# 02_som.net
KiCad netlist of a schematic drawn in Altium Designer
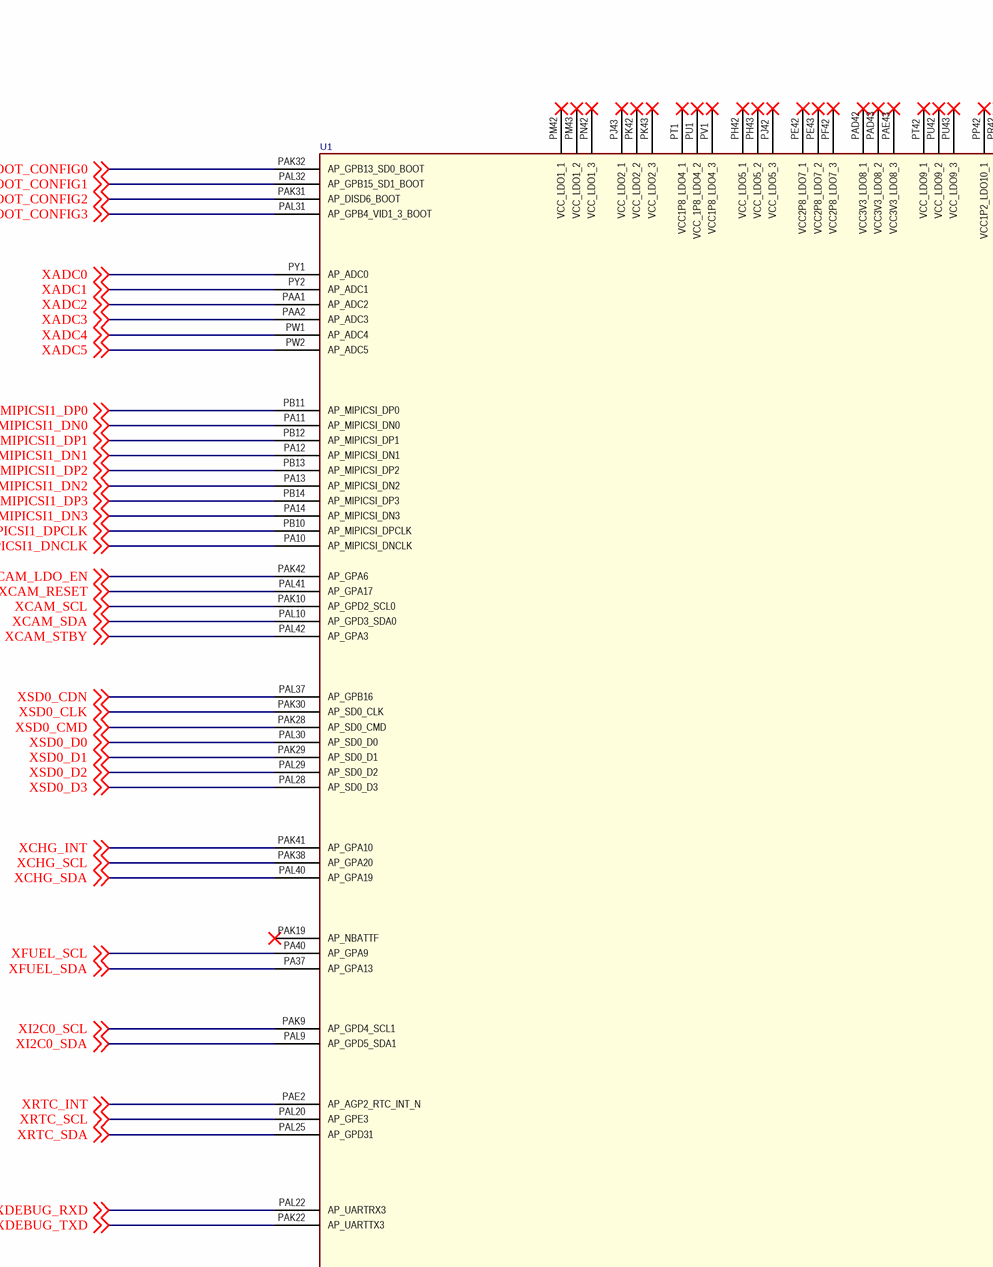
[diagram p0: 02_som.SchDoc, top left]
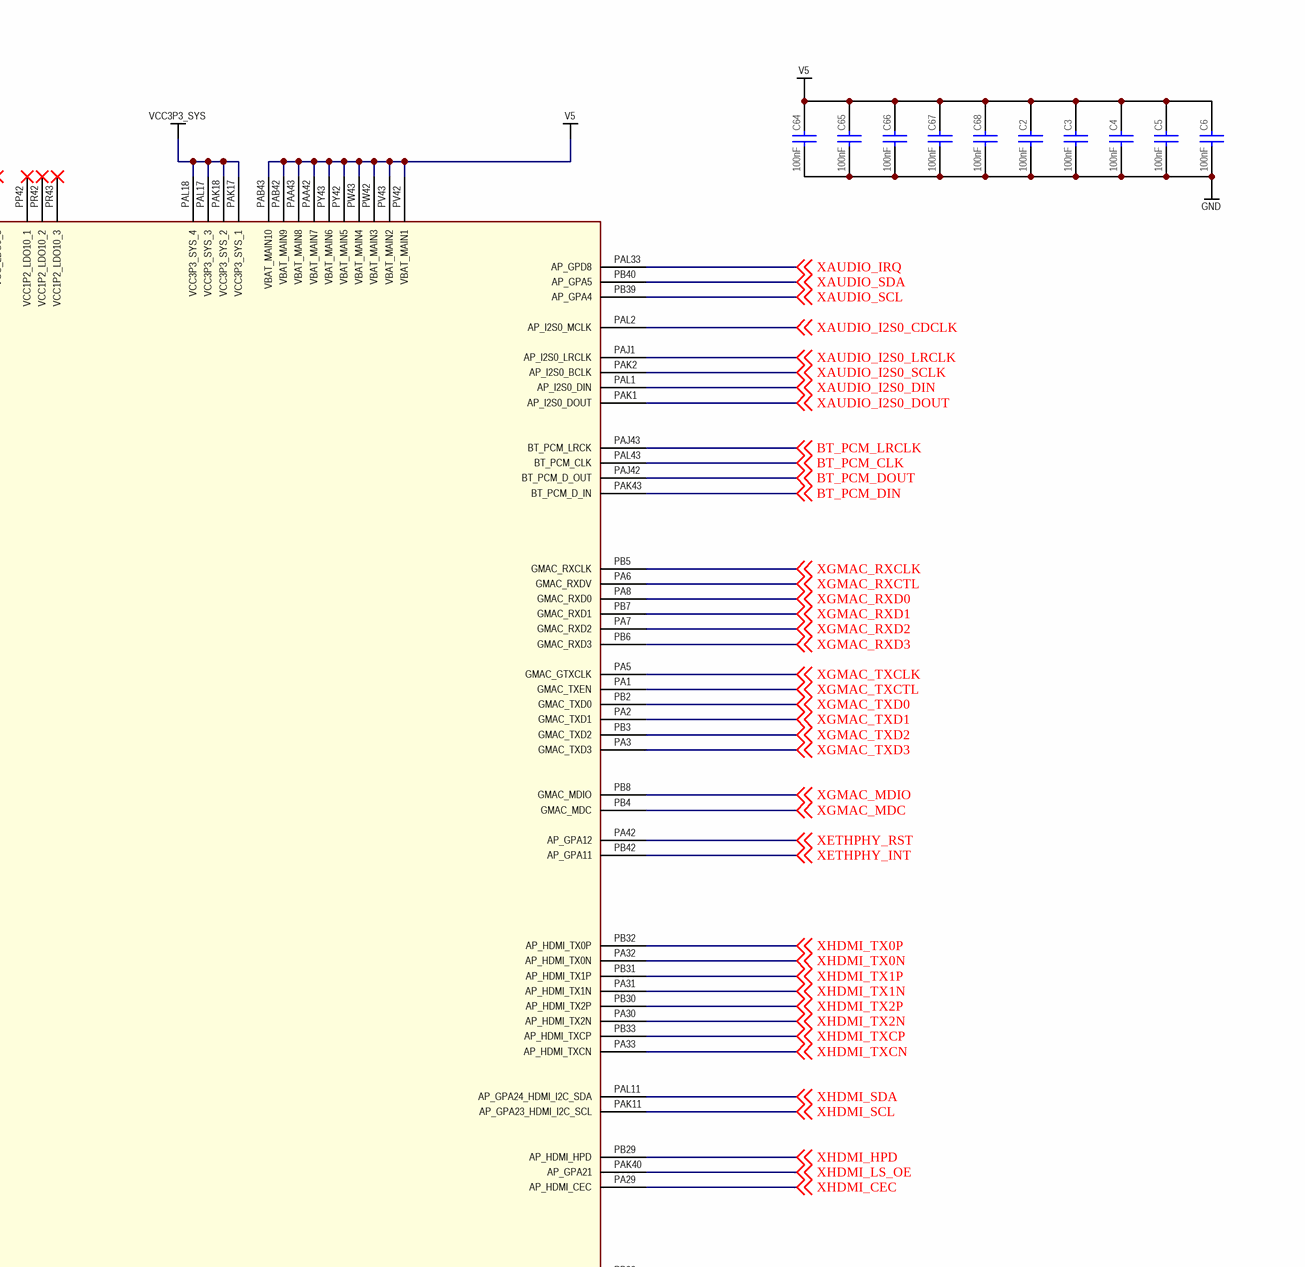
[diagram p1: 02_som.SchDoc, top right]
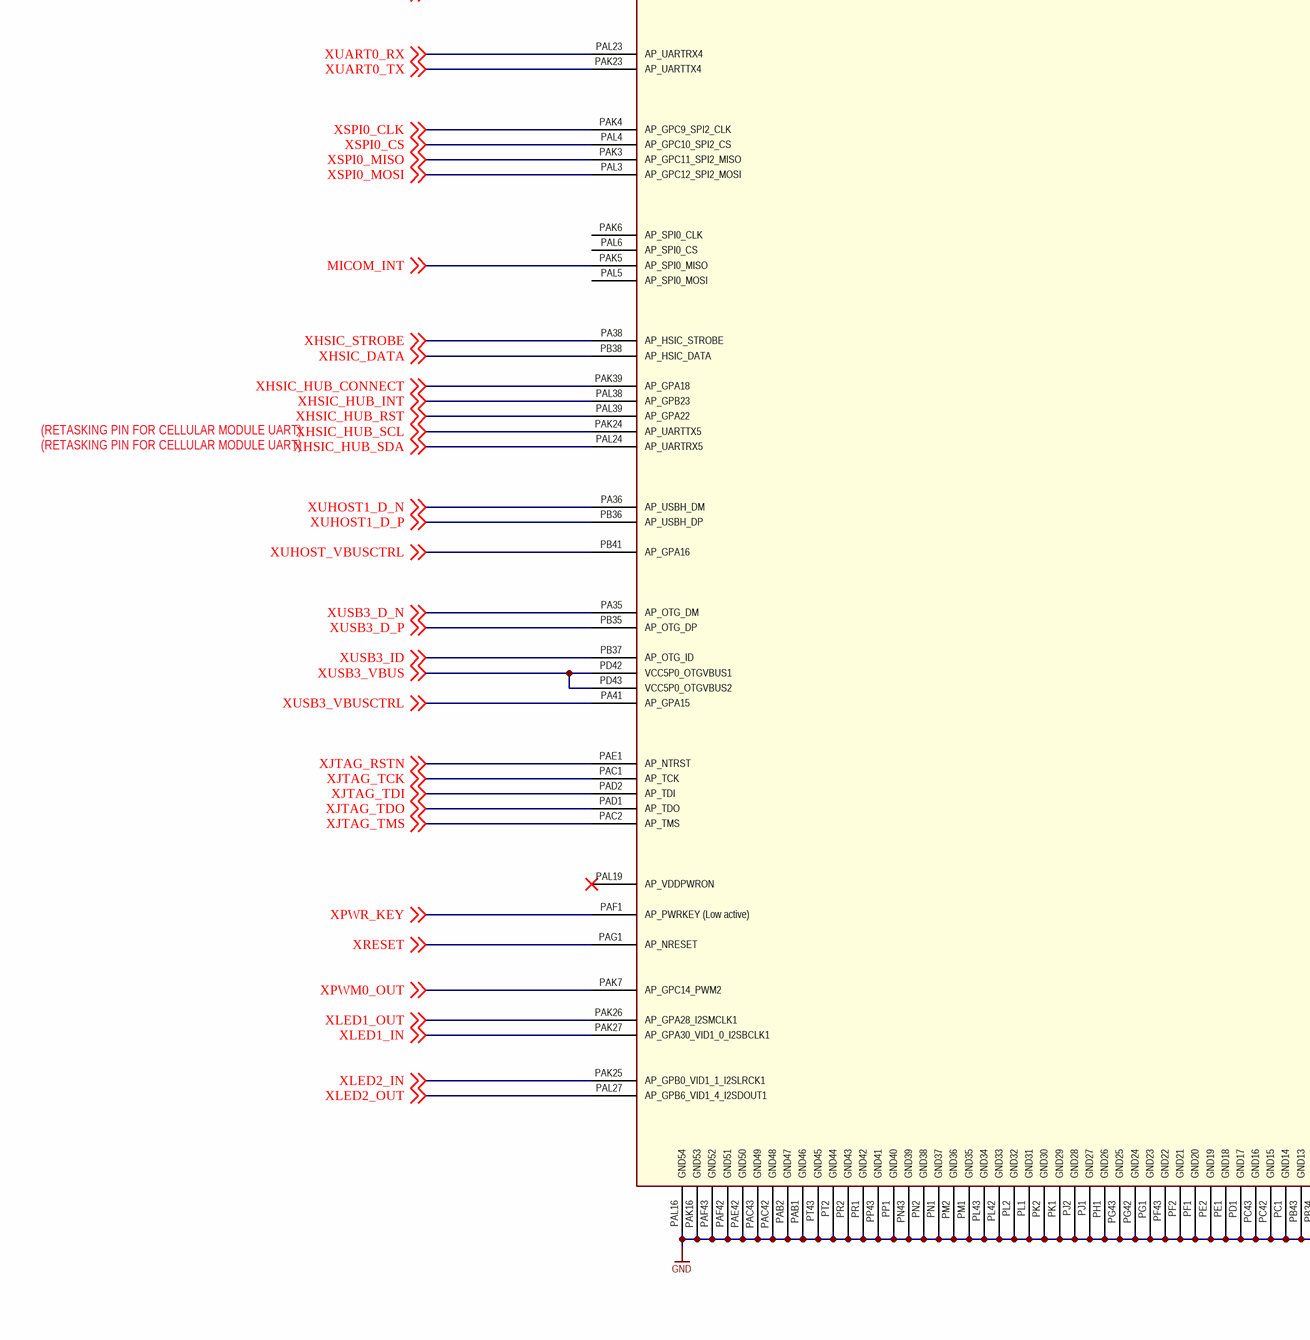
[diagram p2: 02_som.SchDoc, bottom left]
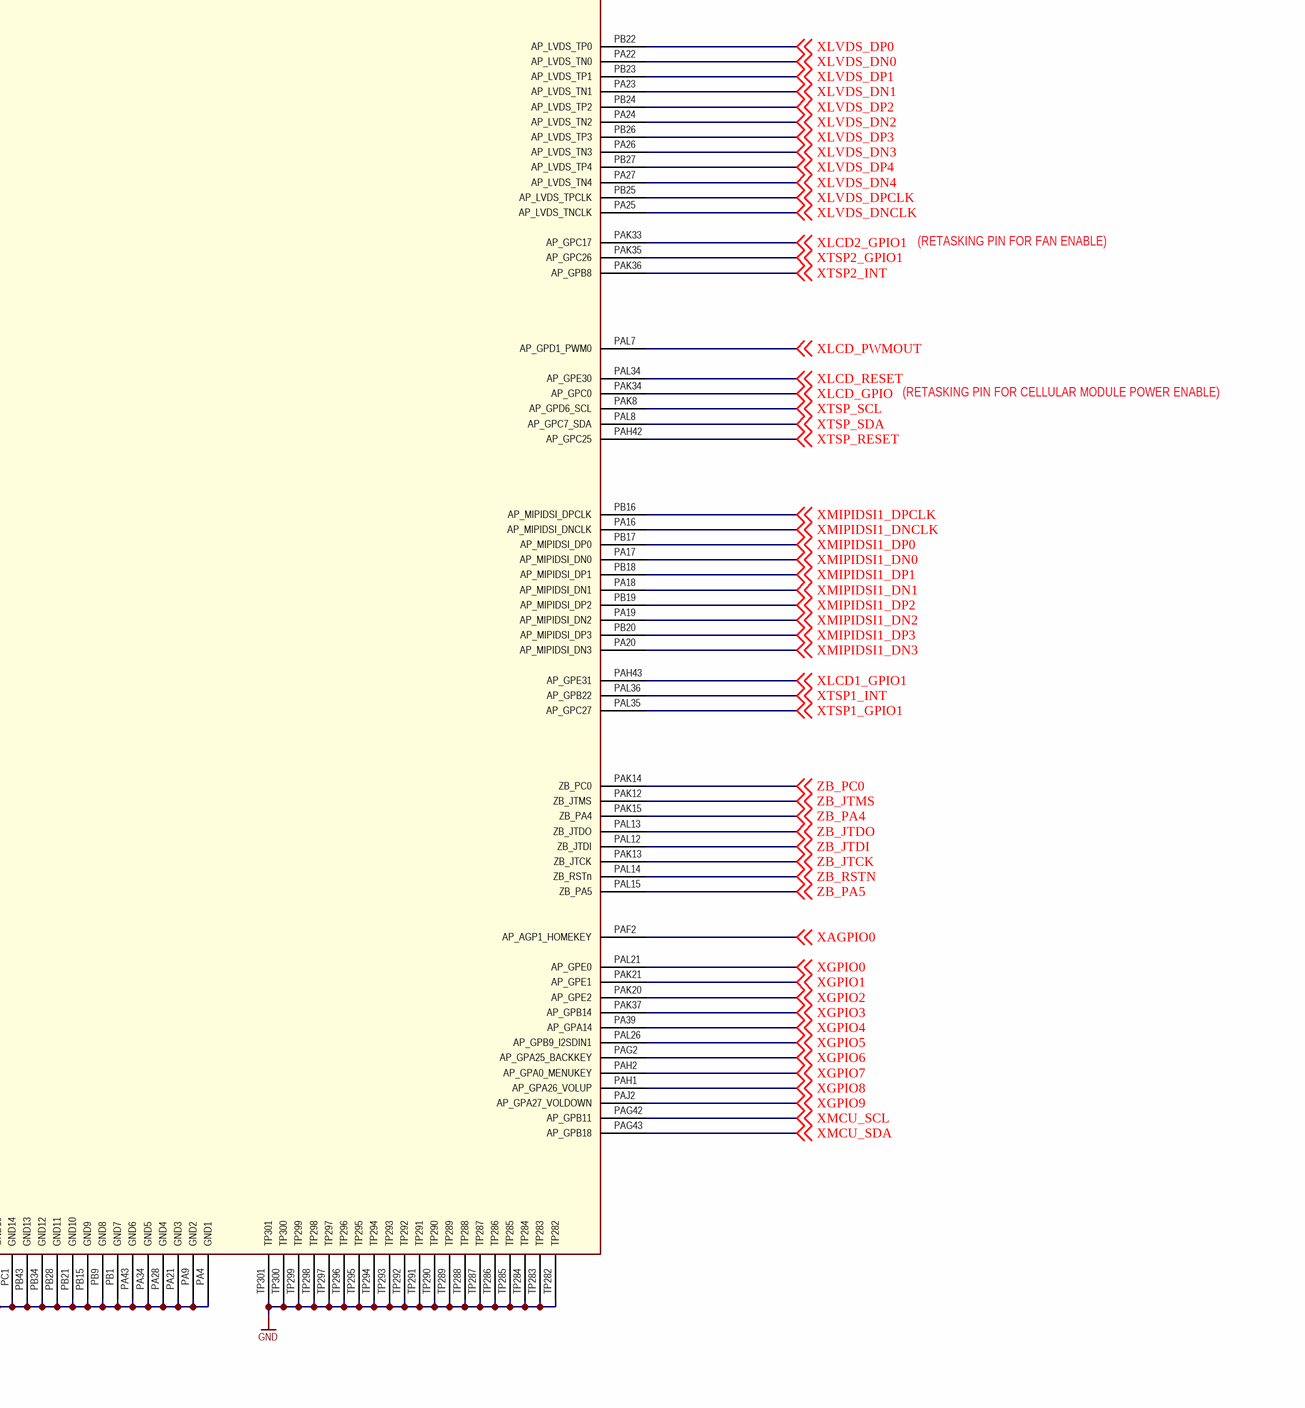
[diagram p3: 02_som.SchDoc, bottom right]

(export (version "E")
  (design (tool "Eeschema 10.0.6"))
  (components
    (comp (ref "C2")
      (value "100nF")
      (footprint "CAPC100X50X55L25N")
      (description "Ceramic Capacitor 100nF ±10% 50V X7R 0402")
      (fields (field (name "MANUFACTURER") "Murata") (field (name "TOLERANCE") "±10%"))
      (libsource (lib "generic") (part "CAP"))
    )
    (comp (ref "C3")
      (value "100nF")
      (footprint "CAPC100X50X55L25N")
      (description "Ceramic Capacitor 100nF ±10% 50V X7R 0402")
      (fields (field (name "MANUFACTURER") "Murata") (field (name "TOLERANCE") "±10%"))
      (libsource (lib "generic") (part "CAP"))
    )
    (comp (ref "C4")
      (value "100nF")
      (footprint "CAPC100X50X55L25N")
      (description "Ceramic Capacitor 100nF ±10% 50V X7R 0402")
      (fields (field (name "MANUFACTURER") "Murata") (field (name "TOLERANCE") "±10%"))
      (libsource (lib "generic") (part "CAP"))
    )
    (comp (ref "C5")
      (value "100nF")
      (footprint "CAPC100X50X55L25N")
      (description "Ceramic Capacitor 100nF ±10% 50V X7R 0402")
      (fields (field (name "MANUFACTURER") "Murata") (field (name "TOLERANCE") "±10%"))
      (libsource (lib "generic") (part "CAP"))
    )
    (comp (ref "C6")
      (value "100nF")
      (footprint "CAPC100X50X55L25N")
      (description "Ceramic Capacitor 100nF ±10% 50V X7R 0402")
      (fields (field (name "MANUFACTURER") "Murata") (field (name "TOLERANCE") "±10%"))
      (libsource (lib "generic") (part "CAP"))
    )
    (comp (ref "C64")
      (value "100nF")
      (footprint "CAPC100X50X55L25N")
      (description "Ceramic Capacitor 100nF ±10% 50V X7R 0402")
      (fields (field (name "MANUFACTURER") "Murata") (field (name "TOLERANCE") "±10%"))
      (libsource (lib "generic") (part "CAP"))
    )
    (comp (ref "C65")
      (value "100nF")
      (footprint "CAPC100X50X55L25N")
      (description "Ceramic Capacitor 100nF ±10% 50V X7R 0402")
      (fields (field (name "MANUFACTURER") "Murata") (field (name "TOLERANCE") "±10%"))
      (libsource (lib "generic") (part "CAP"))
    )
    (comp (ref "C66")
      (value "100nF")
      (footprint "CAPC100X50X55L25N")
      (description "Ceramic Capacitor 100nF ±10% 50V X7R 0402")
      (fields (field (name "MANUFACTURER") "Murata") (field (name "TOLERANCE") "±10%"))
      (libsource (lib "generic") (part "CAP"))
    )
    (comp (ref "C67")
      (value "100nF")
      (footprint "CAPC100X50X55L25N")
      (description "Ceramic Capacitor 100nF ±10% 50V X7R 0402")
      (fields (field (name "MANUFACTURER") "Murata") (field (name "TOLERANCE") "±10%"))
      (libsource (lib "generic") (part "CAP"))
    )
    (comp (ref "C68")
      (value "100nF")
      (footprint "CAPC100X50X55L25N")
      (description "Ceramic Capacitor 100nF ±10% 50V X7R 0402")
      (fields (field (name "MANUFACTURER") "Murata") (field (name "TOLERANCE") "±10%"))
      (libsource (lib "generic") (part "CAP"))
    )
    (comp (ref "U1")
      (value "ARTIK_710_LGA_PAD")
      (footprint "samsung:ARTIK_LGA_PAD_10")
      (description "ARTIK 710 System on Module")
      (fields (field (name "MANUFACTURER") "Samsung"))
      (libsource (lib "*") (part "ARTIK_LGA_PAD_10"))
    )
  )
  (nets
    (net (code "1") (name "BT_PCM_CLK") (class "Default")
      (node (ref "U1") (pin "PAL43") (pinfunction "BT_PCM_CLK_PAL43") (pintype "passive"))
    )
    (net (code "2") (name "BT_PCM_DIN") (class "Default")
      (node (ref "U1") (pin "PAK43") (pinfunction "BT_PCM_D_IN_PAK43") (pintype "passive"))
    )
    (net (code "3") (name "BT_PCM_DOUT") (class "Default")
      (node (ref "U1") (pin "PAJ42") (pinfunction "BT_PCM_D_OUT_PAJ42") (pintype "passive"))
    )
    (net (code "4") (name "BT_PCM_LRCLK") (class "Default")
      (node (ref "U1") (pin "PAJ43") (pinfunction "BT_PCM_LRCK_PAJ43") (pintype "passive"))
    )
    (net (code "5") (name "GND") (class "Default")
      (node (ref "C2") (pin "1") (pinfunction "1_1") (pintype "passive"))
      (node (ref "C3") (pin "1") (pinfunction "1_1") (pintype "passive"))
      (node (ref "C4") (pin "1") (pinfunction "1_1") (pintype "passive"))
      (node (ref "C5") (pin "1") (pinfunction "1_1") (pintype "passive"))
      (node (ref "C6") (pin "1") (pinfunction "1_1") (pintype "passive"))
      (node (ref "C64") (pin "1") (pinfunction "1_1") (pintype "passive"))
      (node (ref "C65") (pin "1") (pinfunction "1_1") (pintype "passive"))
      (node (ref "C66") (pin "1") (pinfunction "1_1") (pintype "passive"))
      (node (ref "C67") (pin "1") (pinfunction "1_1") (pintype "passive"))
      (node (ref "C68") (pin "1") (pinfunction "1_1") (pintype "passive"))
      (node (ref "U1") (pin "PA21") (pinfunction "GND3_PA21") (pintype "passive"))
      (node (ref "U1") (pin "PA28") (pinfunction "GND4_PA28") (pintype "passive"))
      (node (ref "U1") (pin "PA34") (pinfunction "GND5_PA34") (pintype "passive"))
      (node (ref "U1") (pin "PA4") (pinfunction "GND1_PA4") (pintype "passive"))
      (node (ref "U1") (pin "PA43") (pinfunction "GND6_PA43") (pintype "passive"))
      (node (ref "U1") (pin "PA9") (pinfunction "GND2_PA9") (pintype "passive"))
      (node (ref "U1") (pin "PAB1") (pinfunction "GND46_PAB1") (pintype "passive"))
      (node (ref "U1") (pin "PAB2") (pinfunction "GND47_PAB2") (pintype "passive"))
      (node (ref "U1") (pin "PAC42") (pinfunction "GND48_PAC42") (pintype "passive"))
      (node (ref "U1") (pin "PAC43") (pinfunction "GND49_PAC43") (pintype "passive"))
      (node (ref "U1") (pin "PAE42") (pinfunction "GND50_PAE42") (pintype "passive"))
      (node (ref "U1") (pin "PAF42") (pinfunction "GND51_PAF42") (pintype "passive"))
      (node (ref "U1") (pin "PAF43") (pinfunction "GND52_PAF43") (pintype "passive"))
      (node (ref "U1") (pin "PAK16") (pinfunction "GND53_PAK16") (pintype "passive"))
      (node (ref "U1") (pin "PAL16") (pinfunction "GND54_PAL16") (pintype "passive"))
      (node (ref "U1") (pin "PB1") (pinfunction "GND7_PB1") (pintype "passive"))
      (node (ref "U1") (pin "PB15") (pinfunction "GND9_PB15") (pintype "passive"))
      (node (ref "U1") (pin "PB21") (pinfunction "GND10_PB21") (pintype "passive"))
      (node (ref "U1") (pin "PB28") (pinfunction "GND11_PB28") (pintype "passive"))
      (node (ref "U1") (pin "PB34") (pinfunction "GND12_PB34") (pintype "passive"))
      (node (ref "U1") (pin "PB43") (pinfunction "GND13_PB43") (pintype "passive"))
      (node (ref "U1") (pin "PB9") (pinfunction "GND8_PB9") (pintype "passive"))
      (node (ref "U1") (pin "PC1") (pinfunction "GND14_PC1") (pintype "passive"))
      (node (ref "U1") (pin "PC42") (pinfunction "GND15_PC42") (pintype "passive"))
      (node (ref "U1") (pin "PC43") (pinfunction "GND16_PC43") (pintype "passive"))
      (node (ref "U1") (pin "PD1") (pinfunction "GND17_PD1") (pintype "passive"))
      (node (ref "U1") (pin "PE1") (pinfunction "GND18_PE1") (pintype "passive"))
      (node (ref "U1") (pin "PE2") (pinfunction "GND19_PE2") (pintype "passive"))
      (node (ref "U1") (pin "PF1") (pinfunction "GND20_PF1") (pintype "passive"))
      (node (ref "U1") (pin "PF2") (pinfunction "GND21_PF2") (pintype "passive"))
      (node (ref "U1") (pin "PF43") (pinfunction "GND22_PF43") (pintype "passive"))
      (node (ref "U1") (pin "PG1") (pinfunction "GND23_PG1") (pintype "passive"))
      (node (ref "U1") (pin "PG42") (pinfunction "GND24_PG42") (pintype "passive"))
      (node (ref "U1") (pin "PG43") (pinfunction "GND25_PG43") (pintype "passive"))
      (node (ref "U1") (pin "PH1") (pinfunction "GND26_PH1") (pintype "passive"))
      (node (ref "U1") (pin "PJ1") (pinfunction "GND27_PJ1") (pintype "passive"))
      (node (ref "U1") (pin "PJ2") (pinfunction "GND28_PJ2") (pintype "passive"))
      (node (ref "U1") (pin "PK1") (pinfunction "GND29_PK1") (pintype "passive"))
      (node (ref "U1") (pin "PK2") (pinfunction "GND30_PK2") (pintype "passive"))
      (node (ref "U1") (pin "PL1") (pinfunction "GND31_PL1") (pintype "passive"))
      (node (ref "U1") (pin "PL2") (pinfunction "GND32_PL2") (pintype "passive"))
      (node (ref "U1") (pin "PL42") (pinfunction "GND33_PL42") (pintype "passive"))
      (node (ref "U1") (pin "PL43") (pinfunction "GND34_PL43") (pintype "passive"))
      (node (ref "U1") (pin "PM1") (pinfunction "GND35_PM1") (pintype "passive"))
      (node (ref "U1") (pin "PM2") (pinfunction "GND36_PM2") (pintype "passive"))
      (node (ref "U1") (pin "PN1") (pinfunction "GND37_PN1") (pintype "passive"))
      (node (ref "U1") (pin "PN2") (pinfunction "GND38_PN2") (pintype "passive"))
      (node (ref "U1") (pin "PN43") (pinfunction "GND39_PN43") (pintype "passive"))
      (node (ref "U1") (pin "PP1") (pinfunction "GND40_PP1") (pintype "passive"))
      (node (ref "U1") (pin "PP43") (pinfunction "GND41_PP43") (pintype "passive"))
      (node (ref "U1") (pin "PR1") (pinfunction "GND42_PR1") (pintype "passive"))
      (node (ref "U1") (pin "PR2") (pinfunction "GND43_PR2") (pintype "passive"))
      (node (ref "U1") (pin "PT2") (pinfunction "GND44_PT2") (pintype "passive"))
      (node (ref "U1") (pin "PT43") (pinfunction "GND45_PT43") (pintype "passive"))
      (node (ref "U1") (pin "TP282") (pinfunction "TP282_TP282") (pintype "passive"))
      (node (ref "U1") (pin "TP283") (pinfunction "TP283_TP283") (pintype "passive"))
      (node (ref "U1") (pin "TP284") (pinfunction "TP284_TP284") (pintype "passive"))
      (node (ref "U1") (pin "TP285") (pinfunction "TP285_TP285") (pintype "passive"))
      (node (ref "U1") (pin "TP286") (pinfunction "TP286_TP286") (pintype "passive"))
      (node (ref "U1") (pin "TP287") (pinfunction "TP287_TP287") (pintype "passive"))
      (node (ref "U1") (pin "TP288") (pinfunction "TP288_TP288") (pintype "passive"))
      (node (ref "U1") (pin "TP289") (pinfunction "TP289_TP289") (pintype "passive"))
      (node (ref "U1") (pin "TP290") (pinfunction "TP290_TP290") (pintype "passive"))
      (node (ref "U1") (pin "TP291") (pinfunction "TP291_TP291") (pintype "passive"))
      (node (ref "U1") (pin "TP292") (pinfunction "TP292_TP292") (pintype "passive"))
      (node (ref "U1") (pin "TP293") (pinfunction "TP293_TP293") (pintype "passive"))
      (node (ref "U1") (pin "TP294") (pinfunction "TP294_TP294") (pintype "passive"))
      (node (ref "U1") (pin "TP295") (pinfunction "TP295_TP295") (pintype "passive"))
      (node (ref "U1") (pin "TP296") (pinfunction "TP296_TP296") (pintype "passive"))
      (node (ref "U1") (pin "TP297") (pinfunction "TP297_TP297") (pintype "passive"))
      (node (ref "U1") (pin "TP298") (pinfunction "TP298_TP298") (pintype "passive"))
      (node (ref "U1") (pin "TP299") (pinfunction "TP299_TP299") (pintype "passive"))
      (node (ref "U1") (pin "TP300") (pinfunction "TP300_TP300") (pintype "passive"))
      (node (ref "U1") (pin "TP301") (pinfunction "TP301_TP301") (pintype "passive"))
    )
    (net (code "6") (name "MICOM_INT") (class "Default")
      (node (ref "U1") (pin "PAK5") (pinfunction "AP_SPI0_MISO_PAK5") (pintype "passive"))
    )
    (net (code "7") (name "V5") (class "Default")
      (node (ref "C2") (pin "2") (pinfunction "2_2") (pintype "passive"))
      (node (ref "C3") (pin "2") (pinfunction "2_2") (pintype "passive"))
      (node (ref "C4") (pin "2") (pinfunction "2_2") (pintype "passive"))
      (node (ref "C5") (pin "2") (pinfunction "2_2") (pintype "passive"))
      (node (ref "C6") (pin "2") (pinfunction "2_2") (pintype "passive"))
      (node (ref "C64") (pin "2") (pinfunction "2_2") (pintype "passive"))
      (node (ref "C65") (pin "2") (pinfunction "2_2") (pintype "passive"))
      (node (ref "C66") (pin "2") (pinfunction "2_2") (pintype "passive"))
      (node (ref "C67") (pin "2") (pinfunction "2_2") (pintype "passive"))
      (node (ref "C68") (pin "2") (pinfunction "2_2") (pintype "passive"))
      (node (ref "U1") (pin "PAA42") (pinfunction "VBAT_MAIN7_PAA42") (pintype "passive"))
      (node (ref "U1") (pin "PAA43") (pinfunction "VBAT_MAIN8_PAA43") (pintype "passive"))
      (node (ref "U1") (pin "PAB42") (pinfunction "VBAT_MAIN9_PAB42") (pintype "passive"))
      (node (ref "U1") (pin "PAB43") (pinfunction "VBAT_MAIN10_PAB43") (pintype "passive"))
      (node (ref "U1") (pin "PV42") (pinfunction "VBAT_MAIN1_PV42") (pintype "passive"))
      (node (ref "U1") (pin "PV43") (pinfunction "VBAT_MAIN2_PV43") (pintype "passive"))
      (node (ref "U1") (pin "PW42") (pinfunction "VBAT_MAIN3_PW42") (pintype "passive"))
      (node (ref "U1") (pin "PW43") (pinfunction "VBAT_MAIN4_PW43") (pintype "passive"))
      (node (ref "U1") (pin "PY42") (pinfunction "VBAT_MAIN5_PY42") (pintype "passive"))
      (node (ref "U1") (pin "PY43") (pinfunction "VBAT_MAIN6_PY43") (pintype "passive"))
    )
    (net (code "8") (name "VCC3P3_SYS") (class "Default")
      (node (ref "U1") (pin "PAK17") (pinfunction "VCC3P3_SYS_1_PAK17") (pintype "passive"))
      (node (ref "U1") (pin "PAK18") (pinfunction "VCC3P3_SYS_2_PAK18") (pintype "passive"))
      (node (ref "U1") (pin "PAL17") (pinfunction "VCC3P3_SYS_3_PAL17") (pintype "passive"))
      (node (ref "U1") (pin "PAL18") (pinfunction "VCC3P3_SYS_4_PAL18") (pintype "passive"))
    )
    (net (code "9") (name "XADC0") (class "Default")
      (node (ref "U1") (pin "PY1") (pinfunction "AP_ADC0_PY1") (pintype "passive"))
    )
    (net (code "10") (name "XADC1") (class "Default")
      (node (ref "U1") (pin "PY2") (pinfunction "AP_ADC1_PY2") (pintype "passive"))
    )
    (net (code "11") (name "XADC2") (class "Default")
      (node (ref "U1") (pin "PAA1") (pinfunction "AP_ADC2_PAA1") (pintype "passive"))
    )
    (net (code "12") (name "XADC3") (class "Default")
      (node (ref "U1") (pin "PAA2") (pinfunction "AP_ADC3_PAA2") (pintype "passive"))
    )
    (net (code "13") (name "XADC4") (class "Default")
      (node (ref "U1") (pin "PW1") (pinfunction "AP_ADC4_PW1") (pintype "passive"))
    )
    (net (code "14") (name "XADC5") (class "Default")
      (node (ref "U1") (pin "PW2") (pinfunction "AP_ADC5_PW2") (pintype "passive"))
    )
    (net (code "15") (name "XAGPIO0") (class "Default")
      (node (ref "U1") (pin "PAF2") (pinfunction "AP_AGP1_HOMEKEY_PAF2") (pintype "passive"))
    )
    (net (code "16") (name "XAUDIO_I2S0_CDCLK") (class "Default")
      (node (ref "U1") (pin "PAL2") (pinfunction "AP_I2S0_MCLK_PAL2") (pintype "passive"))
    )
    (net (code "17") (name "XAUDIO_I2S0_DIN") (class "Default")
      (node (ref "U1") (pin "PAL1") (pinfunction "AP_I2S0_DIN_PAL1") (pintype "passive"))
    )
    (net (code "18") (name "XAUDIO_I2S0_DOUT") (class "Default")
      (node (ref "U1") (pin "PAK1") (pinfunction "AP_I2S0_DOUT_PAK1") (pintype "passive"))
    )
    (net (code "19") (name "XAUDIO_I2S0_LRCLK") (class "Default")
      (node (ref "U1") (pin "PAJ1") (pinfunction "AP_I2S0_LRCLK_PAJ1") (pintype "passive"))
    )
    (net (code "20") (name "XAUDIO_I2S0_SCLK") (class "Default")
      (node (ref "U1") (pin "PAK2") (pinfunction "AP_I2S0_BCLK_PAK2") (pintype "passive"))
    )
    (net (code "21") (name "XAUDIO_IRQ") (class "Default")
      (node (ref "U1") (pin "PAL33") (pinfunction "AP_GPD8_PAL33") (pintype "passive"))
    )
    (net (code "22") (name "XAUDIO_SCL") (class "Default")
      (node (ref "U1") (pin "PB39") (pinfunction "AP_GPA4_PB39") (pintype "passive"))
    )
    (net (code "23") (name "XAUDIO_SDA") (class "Default")
      (node (ref "U1") (pin "PB40") (pinfunction "AP_GPA5_PB40") (pintype "passive"))
    )
    (net (code "24") (name "XBOOT_CONFIG0") (class "Default")
      (node (ref "U1") (pin "PAK32") (pinfunction "AP_GPB13_SD0_BOOT_PAK32") (pintype "passive"))
    )
    (net (code "25") (name "XBOOT_CONFIG1") (class "Default")
      (node (ref "U1") (pin "PAL32") (pinfunction "AP_GPB15_SD1_BOOT_PAL32") (pintype "passive"))
    )
    (net (code "26") (name "XBOOT_CONFIG2") (class "Default")
      (node (ref "U1") (pin "PAK31") (pinfunction "AP_DISD6_BOOT_PAK31") (pintype "passive"))
    )
    (net (code "27") (name "XBOOT_CONFIG3") (class "Default")
      (node (ref "U1") (pin "PAL31") (pinfunction "AP_GPB4_VID1_3_BOOT_PAL31") (pintype "passive"))
    )
    (net (code "28") (name "XCAM_LDO_EN") (class "Default")
      (node (ref "U1") (pin "PAK42") (pinfunction "AP_GPA6_PAK42") (pintype "passive"))
    )
    (net (code "29") (name "XCAM_RESET") (class "Default")
      (node (ref "U1") (pin "PAL41") (pinfunction "AP_GPA17_PAL41") (pintype "passive"))
    )
    (net (code "30") (name "XCAM_SCL") (class "Default")
      (node (ref "U1") (pin "PAK10") (pinfunction "AP_GPD2_SCL0_PAK10") (pintype "passive"))
    )
    (net (code "31") (name "XCAM_SDA") (class "Default")
      (node (ref "U1") (pin "PAL10") (pinfunction "AP_GPD3_SDA0_PAL10") (pintype "passive"))
    )
    (net (code "32") (name "XCAM_STBY") (class "Default")
      (node (ref "U1") (pin "PAL42") (pinfunction "AP_GPA3_PAL42") (pintype "passive"))
    )
    (net (code "33") (name "XCHG_INT") (class "Default")
      (node (ref "U1") (pin "PAK41") (pinfunction "AP_GPA10_PAK41") (pintype "passive"))
    )
    (net (code "34") (name "XCHG_SCL") (class "Default")
      (node (ref "U1") (pin "PAK38") (pinfunction "AP_GPA20_PAK38") (pintype "passive"))
    )
    (net (code "35") (name "XCHG_SDA") (class "Default")
      (node (ref "U1") (pin "PAL40") (pinfunction "AP_GPA19_PAL40") (pintype "passive"))
    )
    (net (code "36") (name "XDEBUG_RXD") (class "Default")
      (node (ref "U1") (pin "PAL22") (pinfunction "AP_UARTRX3_PAL22") (pintype "passive"))
    )
    (net (code "37") (name "XDEBUG_TXD") (class "Default")
      (node (ref "U1") (pin "PAK22") (pinfunction "AP_UARTTX3_PAK22") (pintype "passive"))
    )
    (net (code "38") (name "XETHPHY_INT") (class "Default")
      (node (ref "U1") (pin "PB42") (pinfunction "AP_GPA11_PB42") (pintype "passive"))
    )
    (net (code "39") (name "XETHPHY_RST") (class "Default")
      (node (ref "U1") (pin "PA42") (pinfunction "AP_GPA12_PA42") (pintype "passive"))
    )
    (net (code "40") (name "XFUEL_SCL") (class "Default")
      (node (ref "U1") (pin "PA40") (pinfunction "AP_GPA9_PA40") (pintype "passive"))
    )
    (net (code "41") (name "XFUEL_SDA") (class "Default")
      (node (ref "U1") (pin "PA37") (pinfunction "AP_GPA13_PA37") (pintype "passive"))
    )
    (net (code "42") (name "XGMAC_MDC") (class "Default")
      (node (ref "U1") (pin "PB4") (pinfunction "GMAC_MDC_PB4") (pintype "passive"))
    )
    (net (code "43") (name "XGMAC_MDIO") (class "Default")
      (node (ref "U1") (pin "PB8") (pinfunction "GMAC_MDIO_PB8") (pintype "passive"))
    )
    (net (code "44") (name "XGMAC_RXCLK") (class "Default")
      (node (ref "U1") (pin "PB5") (pinfunction "GMAC_RXCLK_PB5") (pintype "passive"))
    )
    (net (code "45") (name "XGMAC_RXCTL") (class "Default")
      (node (ref "U1") (pin "PA6") (pinfunction "GMAC_RXDV_PA6") (pintype "passive"))
    )
    (net (code "46") (name "XGMAC_RXD0") (class "Default")
      (node (ref "U1") (pin "PA8") (pinfunction "GMAC_RXD0_PA8") (pintype "passive"))
    )
    (net (code "47") (name "XGMAC_RXD1") (class "Default")
      (node (ref "U1") (pin "PB7") (pinfunction "GMAC_RXD1_PB7") (pintype "passive"))
    )
    (net (code "48") (name "XGMAC_RXD2") (class "Default")
      (node (ref "U1") (pin "PA7") (pinfunction "GMAC_RXD2_PA7") (pintype "passive"))
    )
    (net (code "49") (name "XGMAC_RXD3") (class "Default")
      (node (ref "U1") (pin "PB6") (pinfunction "GMAC_RXD3_PB6") (pintype "passive"))
    )
    (net (code "50") (name "XGMAC_TXCLK") (class "Default")
      (node (ref "U1") (pin "PA5") (pinfunction "GMAC_GTXCLK_PA5") (pintype "passive"))
    )
    (net (code "51") (name "XGMAC_TXCTL") (class "Default")
      (node (ref "U1") (pin "PA1") (pinfunction "GMAC_TXEN_PA1") (pintype "passive"))
    )
    (net (code "52") (name "XGMAC_TXD0") (class "Default")
      (node (ref "U1") (pin "PB2") (pinfunction "GMAC_TXD0_PB2") (pintype "passive"))
    )
    (net (code "53") (name "XGMAC_TXD1") (class "Default")
      (node (ref "U1") (pin "PA2") (pinfunction "GMAC_TXD1_PA2") (pintype "passive"))
    )
    (net (code "54") (name "XGMAC_TXD2") (class "Default")
      (node (ref "U1") (pin "PB3") (pinfunction "GMAC_TXD2_PB3") (pintype "passive"))
    )
    (net (code "55") (name "XGMAC_TXD3") (class "Default")
      (node (ref "U1") (pin "PA3") (pinfunction "GMAC_TXD3_PA3") (pintype "passive"))
    )
    (net (code "56") (name "XGPIO0") (class "Default")
      (node (ref "U1") (pin "PAL21") (pinfunction "AP_GPE0_PAL21") (pintype "passive"))
    )
    (net (code "57") (name "XGPIO1") (class "Default")
      (node (ref "U1") (pin "PAK21") (pinfunction "AP_GPE1_PAK21") (pintype "passive"))
    )
    (net (code "58") (name "XGPIO2") (class "Default")
      (node (ref "U1") (pin "PAK20") (pinfunction "AP_GPE2_PAK20") (pintype "passive"))
    )
    (net (code "59") (name "XGPIO3") (class "Default")
      (node (ref "U1") (pin "PAK37") (pinfunction "AP_GPB14_PAK37") (pintype "passive"))
    )
    (net (code "60") (name "XGPIO4") (class "Default")
      (node (ref "U1") (pin "PA39") (pinfunction "AP_GPA14_PA39") (pintype "passive"))
    )
    (net (code "61") (name "XGPIO5") (class "Default")
      (node (ref "U1") (pin "PAL26") (pinfunction "AP_GPB9_I2SDIN1_PAL26") (pintype "passive"))
    )
    (net (code "62") (name "XGPIO6") (class "Default")
      (node (ref "U1") (pin "PAG2") (pinfunction "AP_GPA25_BACKKEY_PAG2") (pintype "passive"))
    )
    (net (code "63") (name "XGPIO7") (class "Default")
      (node (ref "U1") (pin "PAH2") (pinfunction "AP_GPA0_MENUKEY_PAH2") (pintype "passive"))
    )
    (net (code "64") (name "XGPIO8") (class "Default")
      (node (ref "U1") (pin "PAH1") (pinfunction "AP_GPA26_VOLUP_PAH1") (pintype "passive"))
    )
    (net (code "65") (name "XGPIO9") (class "Default")
      (node (ref "U1") (pin "PAJ2") (pinfunction "AP_GPA27_VOLDOWN_PAJ2") (pintype "passive"))
    )
    (net (code "66") (name "XHDMI_CEC") (class "Default")
      (node (ref "U1") (pin "PA29") (pinfunction "AP_HDMI_CEC_PA29") (pintype "passive"))
    )
    (net (code "67") (name "XHDMI_HPD") (class "Default")
      (node (ref "U1") (pin "PB29") (pinfunction "AP_HDMI_HPD_PB29") (pintype "passive"))
    )
    (net (code "68") (name "XHDMI_LS_OE") (class "Default")
      (node (ref "U1") (pin "PAK40") (pinfunction "AP_GPA21_PAK40") (pintype "passive"))
    )
    (net (code "69") (name "XHDMI_SCL") (class "Default")
      (node (ref "U1") (pin "PAK11") (pinfunction "AP_GPA23_HDMI_I2C_SCL_PAK11") (pintype "passive"))
    )
    (net (code "70") (name "XHDMI_SDA") (class "Default")
      (node (ref "U1") (pin "PAL11") (pinfunction "AP_GPA24_HDMI_I2C_SDA_PAL11") (pintype "passive"))
    )
    (net (code "71") (name "XHDMI_TX0N") (class "Default")
      (node (ref "U1") (pin "PA32") (pinfunction "AP_HDMI_TX0N_PA32") (pintype "passive"))
    )
    (net (code "72") (name "XHDMI_TX0P") (class "Default")
      (node (ref "U1") (pin "PB32") (pinfunction "AP_HDMI_TX0P_PB32") (pintype "passive"))
    )
    (net (code "73") (name "XHDMI_TX1N") (class "Default")
      (node (ref "U1") (pin "PA31") (pinfunction "AP_HDMI_TX1N_PA31") (pintype "passive"))
    )
    (net (code "74") (name "XHDMI_TX1P") (class "Default")
      (node (ref "U1") (pin "PB31") (pinfunction "AP_HDMI_TX1P_PB31") (pintype "passive"))
    )
    (net (code "75") (name "XHDMI_TX2N") (class "Default")
      (node (ref "U1") (pin "PA30") (pinfunction "AP_HDMI_TX2N_PA30") (pintype "passive"))
    )
    (net (code "76") (name "XHDMI_TX2P") (class "Default")
      (node (ref "U1") (pin "PB30") (pinfunction "AP_HDMI_TX2P_PB30") (pintype "passive"))
    )
    (net (code "77") (name "XHDMI_TXCN") (class "Default")
      (node (ref "U1") (pin "PA33") (pinfunction "AP_HDMI_TXCN_PA33") (pintype "passive"))
    )
    (net (code "78") (name "XHDMI_TXCP") (class "Default")
      (node (ref "U1") (pin "PB33") (pinfunction "AP_HDMI_TXCP_PB33") (pintype "passive"))
    )
    (net (code "79") (name "XHSIC_DATA") (class "Default")
      (node (ref "U1") (pin "PB38") (pinfunction "AP_HSIC_DATA_PB38") (pintype "passive"))
    )
    (net (code "80") (name "XHSIC_HUB_CONNECT") (class "Default")
      (node (ref "U1") (pin "PAK39") (pinfunction "AP_GPA18_PAK39") (pintype "passive"))
    )
    (net (code "81") (name "XHSIC_HUB_INT") (class "Default")
      (node (ref "U1") (pin "PAL38") (pinfunction "AP_GPB23_PAL38") (pintype "passive"))
    )
    (net (code "82") (name "XHSIC_HUB_RST") (class "Default")
      (node (ref "U1") (pin "PAL39") (pinfunction "AP_GPA22_PAL39") (pintype "passive"))
    )
    (net (code "83") (name "XHSIC_HUB_SCL") (class "Default")
      (node (ref "U1") (pin "PAK24") (pinfunction "AP_UARTTX5_PAK24") (pintype "passive"))
    )
    (net (code "84") (name "XHSIC_HUB_SDA") (class "Default")
      (node (ref "U1") (pin "PAL24") (pinfunction "AP_UARTRX5_PAL24") (pintype "passive"))
    )
    (net (code "85") (name "XHSIC_STROBE") (class "Default")
      (node (ref "U1") (pin "PA38") (pinfunction "AP_HSIC_STROBE_PA38") (pintype "passive"))
    )
    (net (code "86") (name "XI2C0_SCL") (class "Default")
      (node (ref "U1") (pin "PAK9") (pinfunction "AP_GPD4_SCL1_PAK9") (pintype "passive"))
    )
    (net (code "87") (name "XI2C0_SDA") (class "Default")
      (node (ref "U1") (pin "PAL9") (pinfunction "AP_GPD5_SDA1_PAL9") (pintype "passive"))
    )
    (net (code "88") (name "XJTAG_RSTN") (class "Default")
      (node (ref "U1") (pin "PAE1") (pinfunction "AP_NTRST_PAE1") (pintype "passive"))
    )
    (net (code "89") (name "XJTAG_TCK") (class "Default")
      (node (ref "U1") (pin "PAC1") (pinfunction "AP_TCK_PAC1") (pintype "passive"))
    )
    (net (code "90") (name "XJTAG_TDI") (class "Default")
      (node (ref "U1") (pin "PAD2") (pinfunction "AP_TDI_PAD2") (pintype "passive"))
    )
    (net (code "91") (name "XJTAG_TDO") (class "Default")
      (node (ref "U1") (pin "PAD1") (pinfunction "AP_TDO_PAD1") (pintype "passive"))
    )
    (net (code "92") (name "XJTAG_TMS") (class "Default")
      (node (ref "U1") (pin "PAC2") (pinfunction "AP_TMS_PAC2") (pintype "passive"))
    )
    (net (code "93") (name "XLCD1_GPIO1") (class "Default")
      (node (ref "U1") (pin "PAH43") (pinfunction "AP_GPE31_PAH43") (pintype "passive"))
    )
    (net (code "94") (name "XLCD2_GPIO1") (class "Default")
      (node (ref "U1") (pin "PAK33") (pinfunction "AP_GPC17_PAK33") (pintype "passive"))
    )
    (net (code "95") (name "XLCD_GPIO") (class "Default")
      (node (ref "U1") (pin "PAK34") (pinfunction "AP_GPC0_PAK34") (pintype "passive"))
    )
    (net (code "96") (name "XLCD_PWMOUT") (class "Default")
      (node (ref "U1") (pin "PAL7") (pinfunction "AP_GPD1_PWM0_PAL7") (pintype "passive"))
    )
    (net (code "97") (name "XLCD_RESET") (class "Default")
      (node (ref "U1") (pin "PAL34") (pinfunction "AP_GPE30_PAL34") (pintype "passive"))
    )
    (net (code "98") (name "XLED1_IN") (class "Default")
      (node (ref "U1") (pin "PAK27") (pinfunction "AP_GPA30_VID1_0_I2SBCLK1_PAK27") (pintype "passive"))
    )
    (net (code "99") (name "XLED1_OUT") (class "Default")
      (node (ref "U1") (pin "PAK26") (pinfunction "AP_GPA28_I2SMCLK1_PAK26") (pintype "passive"))
    )
    (net (code "100") (name "XLED2_IN") (class "Default")
      (node (ref "U1") (pin "PAK25") (pinfunction "AP_GPB0_VID1_1_I2SLRCK1_PAK25") (pintype "passive"))
    )
    (net (code "101") (name "XLED2_OUT") (class "Default")
      (node (ref "U1") (pin "PAL27") (pinfunction "AP_GPB6_VID1_4_I2SDOUT1_PAL27") (pintype "passive"))
    )
    (net (code "102") (name "XLVDS_DN0") (class "Default")
      (node (ref "U1") (pin "PA22") (pinfunction "AP_LVDS_TN0_PA22") (pintype "passive"))
    )
    (net (code "103") (name "XLVDS_DN1") (class "Default")
      (node (ref "U1") (pin "PA23") (pinfunction "AP_LVDS_TN1_PA23") (pintype "passive"))
    )
    (net (code "104") (name "XLVDS_DN2") (class "Default")
      (node (ref "U1") (pin "PA24") (pinfunction "AP_LVDS_TN2_PA24") (pintype "passive"))
    )
    (net (code "105") (name "XLVDS_DN3") (class "Default")
      (node (ref "U1") (pin "PA26") (pinfunction "AP_LVDS_TN3_PA26") (pintype "passive"))
    )
    (net (code "106") (name "XLVDS_DN4") (class "Default")
      (node (ref "U1") (pin "PA27") (pinfunction "AP_LVDS_TN4_PA27") (pintype "passive"))
    )
    (net (code "107") (name "XLVDS_DNCLK") (class "Default")
      (node (ref "U1") (pin "PA25") (pinfunction "AP_LVDS_TNCLK_PA25") (pintype "passive"))
    )
    (net (code "108") (name "XLVDS_DP0") (class "Default")
      (node (ref "U1") (pin "PB22") (pinfunction "AP_LVDS_TP0_PB22") (pintype "passive"))
    )
    (net (code "109") (name "XLVDS_DP1") (class "Default")
      (node (ref "U1") (pin "PB23") (pinfunction "AP_LVDS_TP1_PB23") (pintype "passive"))
    )
    (net (code "110") (name "XLVDS_DP2") (class "Default")
      (node (ref "U1") (pin "PB24") (pinfunction "AP_LVDS_TP2_PB24") (pintype "passive"))
    )
    (net (code "111") (name "XLVDS_DP3") (class "Default")
      (node (ref "U1") (pin "PB26") (pinfunction "AP_LVDS_TP3_PB26") (pintype "passive"))
    )
    (net (code "112") (name "XLVDS_DP4") (class "Default")
      (node (ref "U1") (pin "PB27") (pinfunction "AP_LVDS_TP4_PB27") (pintype "passive"))
    )
    (net (code "113") (name "XLVDS_DPCLK") (class "Default")
      (node (ref "U1") (pin "PB25") (pinfunction "AP_LVDS_TPCLK_PB25") (pintype "passive"))
    )
    (net (code "114") (name "XMCU_SCL") (class "Default")
      (node (ref "U1") (pin "PAG42") (pinfunction "AP_GPB11_PAG42") (pintype "passive"))
    )
    (net (code "115") (name "XMCU_SDA") (class "Default")
      (node (ref "U1") (pin "PAG43") (pinfunction "AP_GPB18_PAG43") (pintype "passive"))
    )
    (net (code "116") (name "XMIPICSI1_DN0") (class "Default")
      (node (ref "U1") (pin "PA11") (pinfunction "AP_MIPICSI_DN0_PA11") (pintype "passive"))
    )
    (net (code "117") (name "XMIPICSI1_DN1") (class "Default")
      (node (ref "U1") (pin "PA12") (pinfunction "AP_MIPICSI_DN1_PA12") (pintype "passive"))
    )
    (net (code "118") (name "XMIPICSI1_DN2") (class "Default")
      (node (ref "U1") (pin "PA13") (pinfunction "AP_MIPICSI_DN2_PA13") (pintype "passive"))
    )
    (net (code "119") (name "XMIPICSI1_DN3") (class "Default")
      (node (ref "U1") (pin "PA14") (pinfunction "AP_MIPICSI_DN3_PA14") (pintype "passive"))
    )
    (net (code "120") (name "XMIPICSI1_DNCLK") (class "Default")
      (node (ref "U1") (pin "PA10") (pinfunction "AP_MIPICSI_DNCLK_PA10") (pintype "passive"))
    )
    (net (code "121") (name "XMIPICSI1_DP0") (class "Default")
      (node (ref "U1") (pin "PB11") (pinfunction "AP_MIPICSI_DP0_PB11") (pintype "passive"))
    )
    (net (code "122") (name "XMIPICSI1_DP1") (class "Default")
      (node (ref "U1") (pin "PB12") (pinfunction "AP_MIPICSI_DP1_PB12") (pintype "passive"))
    )
    (net (code "123") (name "XMIPICSI1_DP2") (class "Default")
      (node (ref "U1") (pin "PB13") (pinfunction "AP_MIPICSI_DP2_PB13") (pintype "passive"))
    )
    (net (code "124") (name "XMIPICSI1_DP3") (class "Default")
      (node (ref "U1") (pin "PB14") (pinfunction "AP_MIPICSI_DP3_PB14") (pintype "passive"))
    )
    (net (code "125") (name "XMIPICSI1_DPCLK") (class "Default")
      (node (ref "U1") (pin "PB10") (pinfunction "AP_MIPICSI_DPCLK_PB10") (pintype "passive"))
    )
    (net (code "126") (name "XMIPIDSI1_DN0") (class "Default")
      (node (ref "U1") (pin "PA17") (pinfunction "AP_MIPIDSI_DN0_PA17") (pintype "passive"))
    )
    (net (code "127") (name "XMIPIDSI1_DN1") (class "Default")
      (node (ref "U1") (pin "PA18") (pinfunction "AP_MIPIDSI_DN1_PA18") (pintype "passive"))
    )
    (net (code "128") (name "XMIPIDSI1_DN2") (class "Default")
      (node (ref "U1") (pin "PA19") (pinfunction "AP_MIPIDSI_DN2_PA19") (pintype "passive"))
    )
    (net (code "129") (name "XMIPIDSI1_DN3") (class "Default")
      (node (ref "U1") (pin "PA20") (pinfunction "AP_MIPIDSI_DN3_PA20") (pintype "passive"))
    )
    (net (code "130") (name "XMIPIDSI1_DNCLK") (class "Default")
      (node (ref "U1") (pin "PA16") (pinfunction "AP_MIPIDSI_DNCLK_PA16") (pintype "passive"))
    )
    (net (code "131") (name "XMIPIDSI1_DP0") (class "Default")
      (node (ref "U1") (pin "PB17") (pinfunction "AP_MIPIDSI_DP0_PB17") (pintype "passive"))
    )
    (net (code "132") (name "XMIPIDSI1_DP1") (class "Default")
      (node (ref "U1") (pin "PB18") (pinfunction "AP_MIPIDSI_DP1_PB18") (pintype "passive"))
    )
    (net (code "133") (name "XMIPIDSI1_DP2") (class "Default")
      (node (ref "U1") (pin "PB19") (pinfunction "AP_MIPIDSI_DP2_PB19") (pintype "passive"))
    )
    (net (code "134") (name "XMIPIDSI1_DP3") (class "Default")
      (node (ref "U1") (pin "PB20") (pinfunction "AP_MIPIDSI_DP3_PB20") (pintype "passive"))
    )
    (net (code "135") (name "XMIPIDSI1_DPCLK") (class "Default")
      (node (ref "U1") (pin "PB16") (pinfunction "AP_MIPIDSI_DPCLK_PB16") (pintype "passive"))
    )
    (net (code "136") (name "XPWM0_OUT") (class "Default")
      (node (ref "U1") (pin "PAK7") (pinfunction "AP_GPC14_PWM2_PAK7") (pintype "passive"))
    )
    (net (code "137") (name "XPWR_KEY") (class "Default")
      (node (ref "U1") (pin "PAF1") (pinfunction "AP_PWRKEY_(Low_active)_PAF1") (pintype "passive"))
    )
    (net (code "138") (name "XRESET") (class "Default")
      (node (ref "U1") (pin "PAG1") (pinfunction "AP_NRESET_PAG1") (pintype "passive"))
    )
    (net (code "139") (name "XRTC_INT") (class "Default")
      (node (ref "U1") (pin "PAE2") (pinfunction "AP_AGP2_RTC_INT_N_PAE2") (pintype "passive"))
    )
    (net (code "140") (name "XRTC_SCL") (class "Default")
      (node (ref "U1") (pin "PAL20") (pinfunction "AP_GPE3_PAL20") (pintype "passive"))
    )
    (net (code "141") (name "XRTC_SDA") (class "Default")
      (node (ref "U1") (pin "PAL25") (pinfunction "AP_GPD31_PAL25") (pintype "passive"))
    )
    (net (code "142") (name "XSD0_CDN") (class "Default")
      (node (ref "U1") (pin "PAL37") (pinfunction "AP_GPB16_PAL37") (pintype "passive"))
    )
    (net (code "143") (name "XSD0_CLK") (class "Default")
      (node (ref "U1") (pin "PAK30") (pinfunction "AP_SD0_CLK_PAK30") (pintype "passive"))
    )
    (net (code "144") (name "XSD0_CMD") (class "Default")
      (node (ref "U1") (pin "PAK28") (pinfunction "AP_SD0_CMD_PAK28") (pintype "passive"))
    )
    (net (code "145") (name "XSD0_D0") (class "Default")
      (node (ref "U1") (pin "PAL30") (pinfunction "AP_SD0_D0_PAL30") (pintype "passive"))
    )
    (net (code "146") (name "XSD0_D1") (class "Default")
      (node (ref "U1") (pin "PAK29") (pinfunction "AP_SD0_D1_PAK29") (pintype "passive"))
    )
    (net (code "147") (name "XSD0_D2") (class "Default")
      (node (ref "U1") (pin "PAL29") (pinfunction "AP_SD0_D2_PAL29") (pintype "passive"))
    )
    (net (code "148") (name "XSD0_D3") (class "Default")
      (node (ref "U1") (pin "PAL28") (pinfunction "AP_SD0_D3_PAL28") (pintype "passive"))
    )
    (net (code "149") (name "XSPI0_CLK") (class "Default")
      (node (ref "U1") (pin "PAK4") (pinfunction "AP_GPC9_SPI2_CLK_PAK4") (pintype "passive"))
    )
    (net (code "150") (name "XSPI0_CS") (class "Default")
      (node (ref "U1") (pin "PAL4") (pinfunction "AP_GPC10_SPI2_CS_PAL4") (pintype "passive"))
    )
    (net (code "151") (name "XSPI0_MISO") (class "Default")
      (node (ref "U1") (pin "PAK3") (pinfunction "AP_GPC11_SPI2_MISO_PAK3") (pintype "passive"))
    )
    (net (code "152") (name "XSPI0_MOSI") (class "Default")
      (node (ref "U1") (pin "PAL3") (pinfunction "AP_GPC12_SPI2_MOSI_PAL3") (pintype "passive"))
    )
    (net (code "153") (name "XTSP1_GPIO1") (class "Default")
      (node (ref "U1") (pin "PAL35") (pinfunction "AP_GPC27_PAL35") (pintype "passive"))
    )
    (net (code "154") (name "XTSP1_INT") (class "Default")
      (node (ref "U1") (pin "PAL36") (pinfunction "AP_GPB22_PAL36") (pintype "passive"))
    )
    (net (code "155") (name "XTSP2_GPIO1") (class "Default")
      (node (ref "U1") (pin "PAK35") (pinfunction "AP_GPC26_PAK35") (pintype "passive"))
    )
    (net (code "156") (name "XTSP2_INT") (class "Default")
      (node (ref "U1") (pin "PAK36") (pinfunction "AP_GPB8_PAK36") (pintype "passive"))
    )
    (net (code "157") (name "XTSP_RESET") (class "Default")
      (node (ref "U1") (pin "PAH42") (pinfunction "AP_GPC25_PAH42") (pintype "passive"))
    )
    (net (code "158") (name "XTSP_SCL") (class "Default")
      (node (ref "U1") (pin "PAK8") (pinfunction "AP_GPD6_SCL_PAK8") (pintype "passive"))
    )
    (net (code "159") (name "XTSP_SDA") (class "Default")
      (node (ref "U1") (pin "PAL8") (pinfunction "AP_GPC7_SDA_PAL8") (pintype "passive"))
    )
    (net (code "160") (name "XUART0_RX") (class "Default")
      (node (ref "U1") (pin "PAL23") (pinfunction "AP_UARTRX4_PAL23") (pintype "passive"))
    )
    (net (code "161") (name "XUART0_TX") (class "Default")
      (node (ref "U1") (pin "PAK23") (pinfunction "AP_UARTTX4_PAK23") (pintype "passive"))
    )
    (net (code "162") (name "XUHOST1_D_N") (class "Default")
      (node (ref "U1") (pin "PA36") (pinfunction "AP_USBH_DM_PA36") (pintype "passive"))
    )
    (net (code "163") (name "XUHOST1_D_P") (class "Default")
      (node (ref "U1") (pin "PB36") (pinfunction "AP_USBH_DP_PB36") (pintype "passive"))
    )
    (net (code "164") (name "XUHOST_VBUSCTRL") (class "Default")
      (node (ref "U1") (pin "PB41") (pinfunction "AP_GPA16_PB41") (pintype "passive"))
    )
    (net (code "165") (name "XUSB3_D_N") (class "Default")
      (node (ref "U1") (pin "PA35") (pinfunction "AP_OTG_DM_PA35") (pintype "passive"))
    )
    (net (code "166") (name "XUSB3_D_P") (class "Default")
      (node (ref "U1") (pin "PB35") (pinfunction "AP_OTG_DP_PB35") (pintype "passive"))
    )
    (net (code "167") (name "XUSB3_ID") (class "Default")
      (node (ref "U1") (pin "PB37") (pinfunction "AP_OTG_ID_PB37") (pintype "passive"))
    )
    (net (code "168") (name "XUSB3_VBUS") (class "Default")
      (node (ref "U1") (pin "PD42") (pinfunction "VCC5P0_OTGVBUS1_PD42") (pintype "passive"))
      (node (ref "U1") (pin "PD43") (pinfunction "VCC5P0_OTGVBUS2_PD43") (pintype "passive"))
    )
    (net (code "169") (name "XUSB3_VBUSCTRL") (class "Default")
      (node (ref "U1") (pin "PA41") (pinfunction "AP_GPA15_PA41") (pintype "passive"))
    )
    (net (code "170") (name "ZB_JTCK") (class "Default")
      (node (ref "U1") (pin "PAK13") (pinfunction "ZB_JTCK_PAK13") (pintype "passive"))
    )
    (net (code "171") (name "ZB_JTDI") (class "Default")
      (node (ref "U1") (pin "PAL12") (pinfunction "ZB_JTDI_PAL12") (pintype "passive"))
    )
    (net (code "172") (name "ZB_JTDO") (class "Default")
      (node (ref "U1") (pin "PAL13") (pinfunction "ZB_JTDO_PAL13") (pintype "passive"))
    )
    (net (code "173") (name "ZB_JTMS") (class "Default")
      (node (ref "U1") (pin "PAK12") (pinfunction "ZB_JTMS_PAK12") (pintype "passive"))
    )
    (net (code "174") (name "ZB_PA4") (class "Default")
      (node (ref "U1") (pin "PAK15") (pinfunction "ZB_PA4_PAK15") (pintype "passive"))
    )
    (net (code "175") (name "ZB_PA5") (class "Default")
      (node (ref "U1") (pin "PAL15") (pinfunction "ZB_PA5_PAL15") (pintype "passive"))
    )
    (net (code "176") (name "ZB_PC0") (class "Default")
      (node (ref "U1") (pin "PAK14") (pinfunction "ZB_PC0_PAK14") (pintype "passive"))
    )
    (net (code "177") (name "ZB_RSTN") (class "Default")
      (node (ref "U1") (pin "PAL14") (pinfunction "ZB_RSTn_PAL14") (pintype "passive"))
    )
    (net (code "178") (name "unconnected-(U1-AP_NBATTF-PadPAK19)") (class "Default")
      (node (ref "U1") (pin "PAK19") (pinfunction "AP_NBATTF_PAK19") (pintype "passive+no_connect"))
    )
    (net (code "179") (name "unconnected-(U1-AP_SPI0_CLK-PadPAK6)") (class "Default")
      (node (ref "U1") (pin "PAK6") (pinfunction "AP_SPI0_CLK_PAK6") (pintype "passive"))
    )
    (net (code "180") (name "unconnected-(U1-AP_SPI0_CS-PadPAL6)") (class "Default")
      (node (ref "U1") (pin "PAL6") (pinfunction "AP_SPI0_CS_PAL6") (pintype "passive"))
    )
    (net (code "181") (name "unconnected-(U1-AP_SPI0_MOSI-PadPAL5)") (class "Default")
      (node (ref "U1") (pin "PAL5") (pinfunction "AP_SPI0_MOSI_PAL5") (pintype "passive"))
    )
    (net (code "182") (name "unconnected-(U1-AP_VDDPWRON-PadPAL19)") (class "Default")
      (node (ref "U1") (pin "PAL19") (pinfunction "AP_VDDPWRON_PAL19") (pintype "passive+no_connect"))
    )
    (net (code "183") (name "unconnected-(U1-VCC1P2_LDO10_1-PadPP42)") (class "Default")
      (node (ref "U1") (pin "PP42") (pinfunction "VCC1P2_LDO10_1_PP42") (pintype "passive+no_connect"))
    )
    (net (code "184") (name "unconnected-(U1-VCC1P2_LDO10_2-PadPR42)") (class "Default")
      (node (ref "U1") (pin "PR42") (pinfunction "VCC1P2_LDO10_2_PR42") (pintype "passive+no_connect"))
    )
    (net (code "185") (name "unconnected-(U1-VCC1P2_LDO10_3-PadPR43)") (class "Default")
      (node (ref "U1") (pin "PR43") (pinfunction "VCC1P2_LDO10_3_PR43") (pintype "passive+no_connect"))
    )
    (net (code "186") (name "unconnected-(U1-VCC1P8_LDO4_1-PadPT1)") (class "Default")
      (node (ref "U1") (pin "PT1") (pinfunction "VCC1P8_LDO4_1_PT1") (pintype "passive+no_connect"))
    )
    (net (code "187") (name "unconnected-(U1-VCC1P8_LDO4_3-PadPV1)") (class "Default")
      (node (ref "U1") (pin "PV1") (pinfunction "VCC1P8_LDO4_3_PV1") (pintype "passive+no_connect"))
    )
    (net (code "188") (name "unconnected-(U1-VCC2P8_LDO7_1-PadPE42)") (class "Default")
      (node (ref "U1") (pin "PE42") (pinfunction "VCC2P8_LDO7_1_PE42") (pintype "passive+no_connect"))
    )
    (net (code "189") (name "unconnected-(U1-VCC2P8_LDO7_2-PadPE43)") (class "Default")
      (node (ref "U1") (pin "PE43") (pinfunction "VCC2P8_LDO7_2_PE43") (pintype "passive+no_connect"))
    )
    (net (code "190") (name "unconnected-(U1-VCC2P8_LDO7_3-PadPF42)") (class "Default")
      (node (ref "U1") (pin "PF42") (pinfunction "VCC2P8_LDO7_3_PF42") (pintype "passive+no_connect"))
    )
    (net (code "191") (name "unconnected-(U1-VCC3V3_LDO8_1-PadPAD42)") (class "Default")
      (node (ref "U1") (pin "PAD42") (pinfunction "VCC3V3_LDO8_1_PAD42") (pintype "passive+no_connect"))
    )
    (net (code "192") (name "unconnected-(U1-VCC3V3_LDO8_2-PadPAD43)") (class "Default")
      (node (ref "U1") (pin "PAD43") (pinfunction "VCC3V3_LDO8_2_PAD43") (pintype "passive+no_connect"))
    )
    (net (code "193") (name "unconnected-(U1-VCC3V3_LDO8_3-PadPAE43)") (class "Default")
      (node (ref "U1") (pin "PAE43") (pinfunction "VCC3V3_LDO8_3_PAE43") (pintype "passive+no_connect"))
    )
    (net (code "194") (name "unconnected-(U1-VCC_1P8_LDO4_2-PadPU1)") (class "Default")
      (node (ref "U1") (pin "PU1") (pinfunction "VCC_1P8_LDO4_2_PU1") (pintype "passive+no_connect"))
    )
    (net (code "195") (name "unconnected-(U1-VCC_LDO1_1-PadPM42)") (class "Default")
      (node (ref "U1") (pin "PM42") (pinfunction "VCC_LDO1_1_PM42") (pintype "passive+no_connect"))
    )
    (net (code "196") (name "unconnected-(U1-VCC_LDO1_2-PadPM43)") (class "Default")
      (node (ref "U1") (pin "PM43") (pinfunction "VCC_LDO1_2_PM43") (pintype "passive+no_connect"))
    )
    (net (code "197") (name "unconnected-(U1-VCC_LDO1_3-PadPN42)") (class "Default")
      (node (ref "U1") (pin "PN42") (pinfunction "VCC_LDO1_3_PN42") (pintype "passive+no_connect"))
    )
    (net (code "198") (name "unconnected-(U1-VCC_LDO2_1-PadPJ43)") (class "Default")
      (node (ref "U1") (pin "PJ43") (pinfunction "VCC_LDO2_1_PJ43") (pintype "passive+no_connect"))
    )
    (net (code "199") (name "unconnected-(U1-VCC_LDO2_2-PadPK42)") (class "Default")
      (node (ref "U1") (pin "PK42") (pinfunction "VCC_LDO2_2_PK42") (pintype "passive+no_connect"))
    )
    (net (code "200") (name "unconnected-(U1-VCC_LDO2_3-PadPK43)") (class "Default")
      (node (ref "U1") (pin "PK43") (pinfunction "VCC_LDO2_3_PK43") (pintype "passive+no_connect"))
    )
    (net (code "201") (name "unconnected-(U1-VCC_LDO5_1-PadPH42)") (class "Default")
      (node (ref "U1") (pin "PH42") (pinfunction "VCC_LDO5_1_PH42") (pintype "passive+no_connect"))
    )
    (net (code "202") (name "unconnected-(U1-VCC_LDO5_2-PadPH43)") (class "Default")
      (node (ref "U1") (pin "PH43") (pinfunction "VCC_LDO5_2_PH43") (pintype "passive+no_connect"))
    )
    (net (code "203") (name "unconnected-(U1-VCC_LDO5_3-PadPJ42)") (class "Default")
      (node (ref "U1") (pin "PJ42") (pinfunction "VCC_LDO5_3_PJ42") (pintype "passive+no_connect"))
    )
    (net (code "204") (name "unconnected-(U1-VCC_LDO9_1-PadPT42)") (class "Default")
      (node (ref "U1") (pin "PT42") (pinfunction "VCC_LDO9_1_PT42") (pintype "passive+no_connect"))
    )
    (net (code "205") (name "unconnected-(U1-VCC_LDO9_2-PadPU42)") (class "Default")
      (node (ref "U1") (pin "PU42") (pinfunction "VCC_LDO9_2_PU42") (pintype "passive+no_connect"))
    )
    (net (code "206") (name "unconnected-(U1-VCC_LDO9_3-PadPU43)") (class "Default")
      (node (ref "U1") (pin "PU43") (pinfunction "VCC_LDO9_3_PU43") (pintype "passive+no_connect"))
    )
  )
)
